# interface.net
KiCad netlist of a schematic drawn in Altium Designer
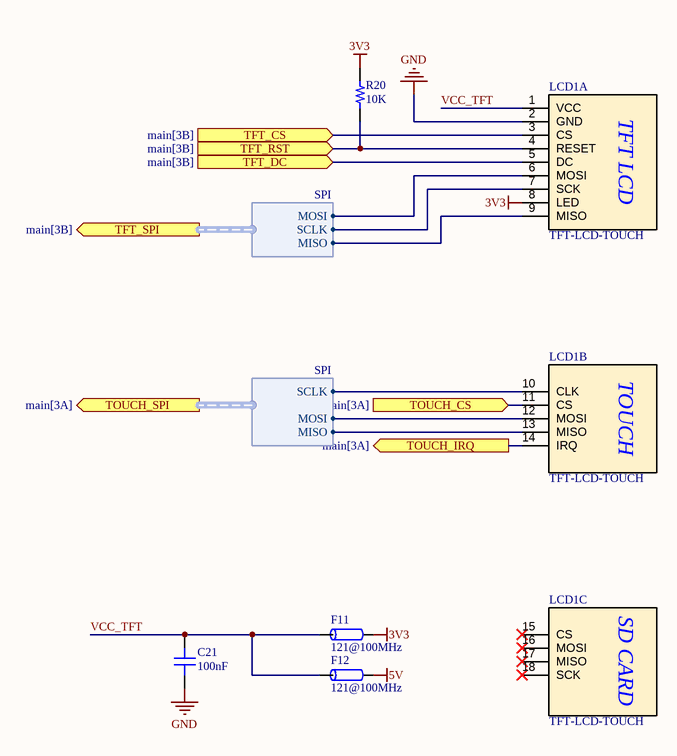
[diagram p0: interface.SchDoc]

(export (version "E")
  (design (tool "Eeschema 10.0.6"))
  (components
    (comp (ref "C21")
      (value "100nF")
      (footprint "CAP 0603_1608")
      (description "SMT Capacitor")
      (libsource (lib "Capacitor") (part "Cap 0603"))
    )
    (comp (ref "F11")
      (value "121@100MHz")
      (footprint "Ferrite-0805")
      (description "Ferrite Bead")
      (libsource (lib "Salman_lib") (part "Ferrite Bead"))
    )
    (comp (ref "F12")
      (value "121@100MHz")
      (footprint "Ferrite-0805")
      (description "Ferrite Bead")
      (libsource (lib "Salman_lib") (part "Ferrite Bead"))
    )
    (comp (ref "LCD1")
      (value "TFT-LCD-TOUCH")
      (footprint "TFT-2.8\"-NO-SCREWS")
      (libsource (lib "Salman_lib") (part "TFT-LCD-TOUCH"))
    )
    (comp (ref "R20")
      (value "10K")
      (footprint "RES 0603_1608")
      (description "SMT Resistor")
      (libsource (lib "Resistor") (part "Res 0603"))
    )
  )
  (nets
    (net (code "2") (name "/TFT_CS") (class "Default")
      (node (ref "LCD1") (pin "3") (pinfunction "CS_3") (pintype "passive"))
    )
    (net (code "3") (name "/TFT_DC") (class "Default")
      (node (ref "LCD1") (pin "5") (pinfunction "DC_5") (pintype "passive"))
    )
    (net (code "4") (name "/TFT_RST") (class "Default")
      (node (ref "LCD1") (pin "4") (pinfunction "RESET_4") (pintype "passive"))
      (node (ref "R20") (pin "1") (pinfunction "1_1") (pintype "passive"))
    )
    (net (code "5") (name "/TOUCH_CS") (class "Default")
      (node (ref "LCD1") (pin "11") (pinfunction "CS_11") (pintype "passive"))
    )
    (net (code "6") (name "/TOUCH_IRQ") (class "Default")
      (node (ref "LCD1") (pin "14") (pinfunction "IRQ_14") (pintype "passive"))
    )
    (net (code "7") (name "/VCC_TFT") (class "Default")
      (node (ref "C21") (pin "2") (pinfunction "2_2") (pintype "passive"))
      (node (ref "F11") (pin "2") (pinfunction "66_2") (pintype "passive"))
      (node (ref "F12") (pin "2") (pinfunction "66_2") (pintype "passive"))
      (node (ref "LCD1") (pin "1") (pinfunction "VCC_1") (pintype "passive"))
    )
    (net (code "9") (name "3V3") (class "Default")
      (node (ref "F11") (pin "1") (pinfunction "67_1") (pintype "passive"))
      (node (ref "LCD1") (pin "8") (pinfunction "LED_8") (pintype "passive"))
      (node (ref "R20") (pin "2") (pinfunction "2_2") (pintype "passive"))
    )
    (net (code "10") (name "5V") (class "Default")
      (node (ref "F12") (pin "1") (pinfunction "67_1") (pintype "passive"))
    )
    (net (code "11") (name "GND") (class "Default")
      (node (ref "C21") (pin "1") (pinfunction "1_1") (pintype "passive"))
      (node (ref "LCD1") (pin "2") (pinfunction "GND_2") (pintype "passive"))
    )
    (net (code "12") (name "unconnected-(LCD1A-MISO-Pad9)") (class "Default")
      (node (ref "LCD1") (pin "9") (pinfunction "MISO_9") (pintype "passive"))
    )
    (net (code "13") (name "unconnected-(LCD1A-MOSI-Pad6)") (class "Default")
      (node (ref "LCD1") (pin "6") (pinfunction "MOSI_6") (pintype "passive"))
    )
    (net (code "14") (name "unconnected-(LCD1A-SCK-Pad7)") (class "Default")
      (node (ref "LCD1") (pin "7") (pinfunction "SCK_7") (pintype "passive"))
    )
    (net (code "15") (name "unconnected-(LCD1B-CLK-Pad10)") (class "Default")
      (node (ref "LCD1") (pin "10") (pinfunction "CLK_10") (pintype "passive"))
    )
    (net (code "16") (name "unconnected-(LCD1B-MISO-Pad13)") (class "Default")
      (node (ref "LCD1") (pin "13") (pinfunction "MISO_13") (pintype "passive"))
    )
    (net (code "17") (name "unconnected-(LCD1B-MOSI-Pad12)") (class "Default")
      (node (ref "LCD1") (pin "12") (pinfunction "MOSI_12") (pintype "passive"))
    )
    (net (code "18") (name "unconnected-(LCD1C-CS-Pad15)") (class "Default")
      (node (ref "LCD1") (pin "15") (pinfunction "CS_15") (pintype "passive+no_connect"))
    )
    (net (code "19") (name "unconnected-(LCD1C-MISO-Pad17)") (class "Default")
      (node (ref "LCD1") (pin "17") (pinfunction "MISO_17") (pintype "passive+no_connect"))
    )
    (net (code "20") (name "unconnected-(LCD1C-MOSI-Pad16)") (class "Default")
      (node (ref "LCD1") (pin "16") (pinfunction "MOSI_16") (pintype "passive+no_connect"))
    )
    (net (code "21") (name "unconnected-(LCD1C-SCK-Pad18)") (class "Default")
      (node (ref "LCD1") (pin "18") (pinfunction "SCK_18") (pintype "passive+no_connect"))
    )
  )
)
